# delay_line.net
KiCad netlist of a schematic drawn in EAGLE
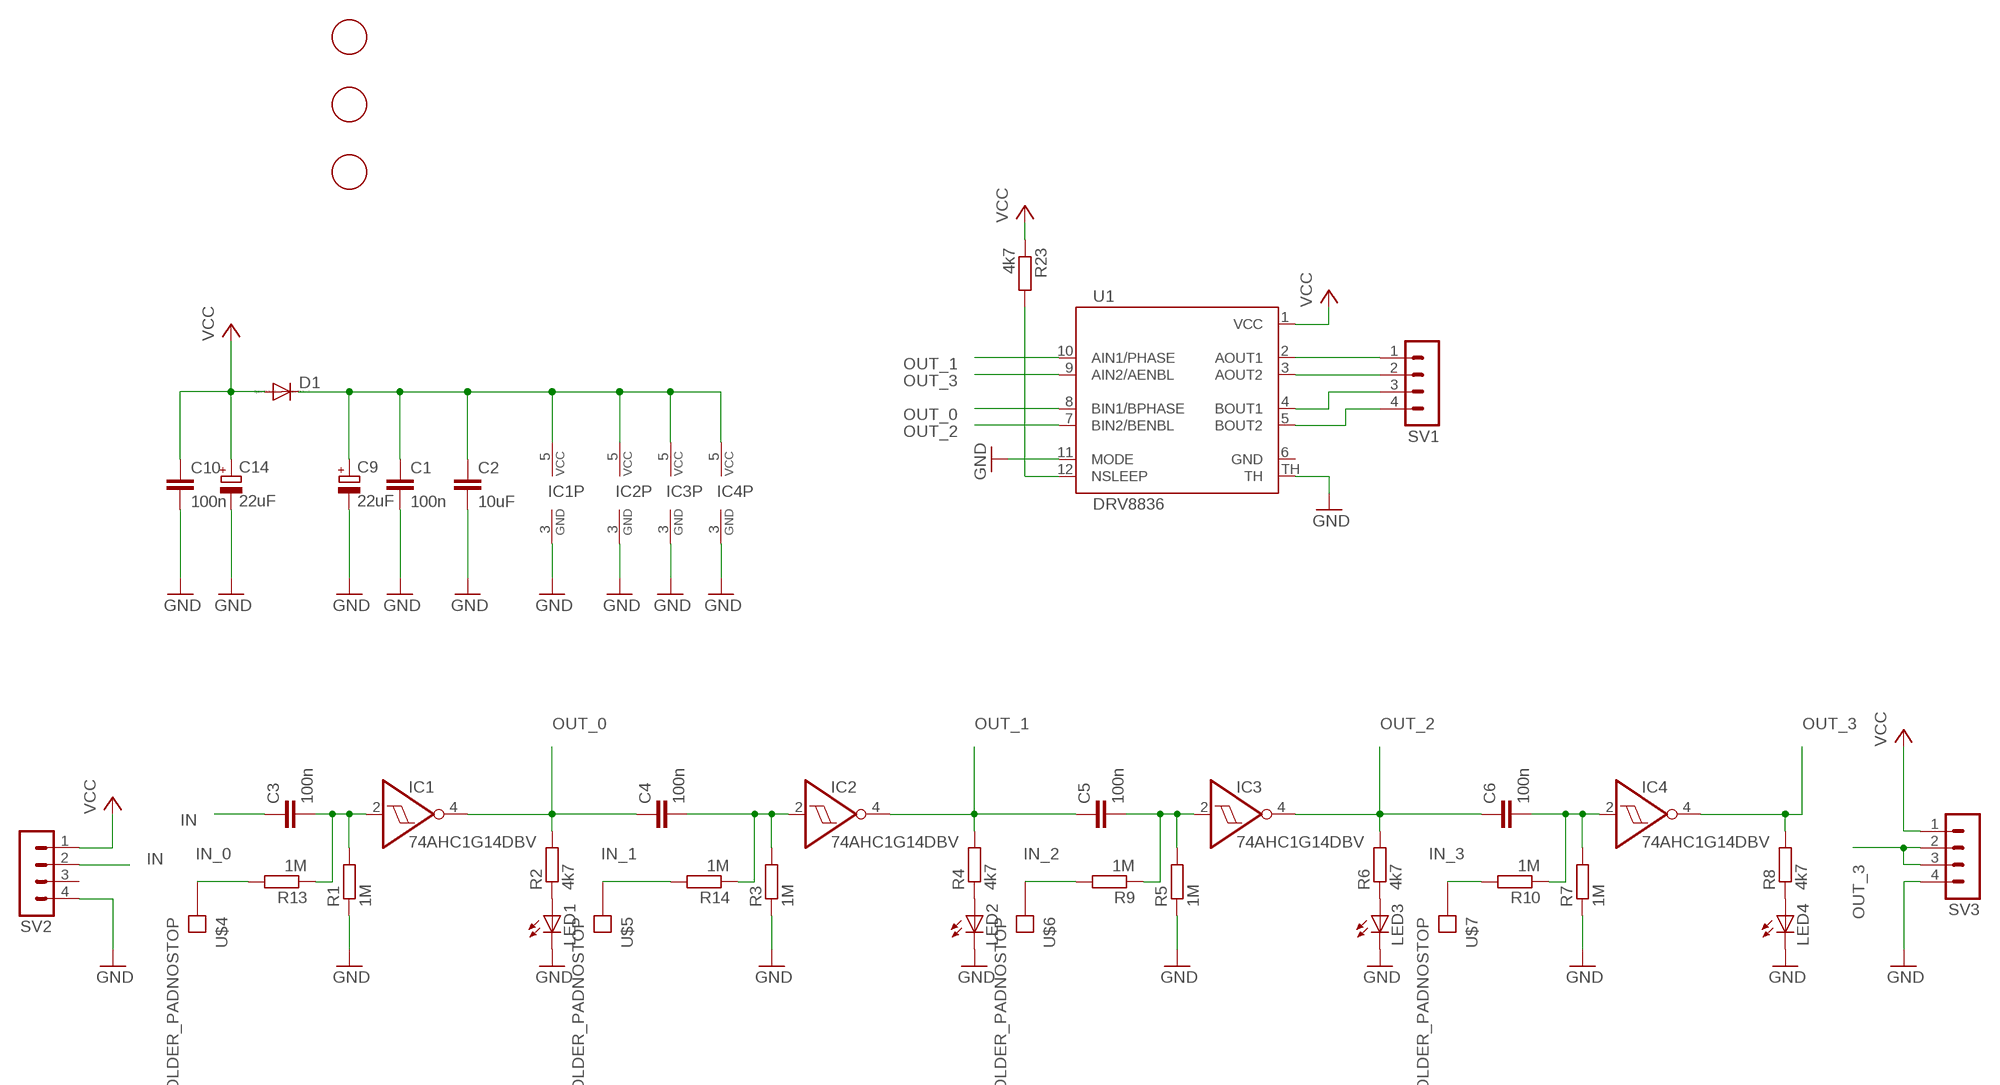
[diagram p0: schematic, sheet 1]

(export (version "E")
  (design (tool "Eeschema 10.0.6"))
  (components
    (comp (ref "C1")
      (value "100n")
      (footprint "eagle-import:C0805")
      (libsource (lib "eagle-import") (part "C-EUC0805"))
    )
    (comp (ref "C2")
      (value "10uF")
      (footprint "eagle-import:C0805")
      (libsource (lib "eagle-import") (part "C-EUC0805"))
    )
    (comp (ref "C3")
      (value "100n")
      (footprint "eagle-import:C0805")
      (libsource (lib "eagle-import") (part "C-EUC0805"))
    )
    (comp (ref "C4")
      (value "100n")
      (footprint "eagle-import:C0805")
      (libsource (lib "eagle-import") (part "C-EUC0805"))
    )
    (comp (ref "C5")
      (value "100n")
      (footprint "eagle-import:C0805")
      (libsource (lib "eagle-import") (part "C-EUC0805"))
    )
    (comp (ref "C6")
      (value "100n")
      (footprint "eagle-import:C0805")
      (libsource (lib "eagle-import") (part "C-EUC0805"))
    )
    (comp (ref "C9")
      (value "22uF")
      (footprint "eagle-import:153CLV-0605")
      (libsource (lib "eagle-import") (part "CPOL-EU153CLV-0605"))
    )
    (comp (ref "C10")
      (value "100n")
      (footprint "eagle-import:C0805")
      (libsource (lib "eagle-import") (part "C-EUC0805"))
    )
    (comp (ref "C14")
      (value "22uF")
      (footprint "eagle-import:153CLV-0605")
      (libsource (lib "eagle-import") (part "CPOL-EU153CLV-0605"))
    )
    (comp (ref "D1")
      (value "DIODE-DO214AA")
      (footprint "eagle-import:DO214AA")
      (libsource (lib "eagle-import") (part "DIODE-DO214AA"))
    )
    (comp (ref "IC1")
      (value "74AHC1G14DBV")
      (footprint "eagle-import:SOT23-5")
      (libsource (lib "eagle-import") (part "741G14DBVAHC"))
    )
    (comp (ref "IC2")
      (value "74AHC1G14DBV")
      (footprint "eagle-import:SOT23-5")
      (libsource (lib "eagle-import") (part "741G14DBVAHC"))
    )
    (comp (ref "IC3")
      (value "74AHC1G14DBV")
      (footprint "eagle-import:SOT23-5")
      (libsource (lib "eagle-import") (part "741G14DBVAHC"))
    )
    (comp (ref "IC4")
      (value "74AHC1G14DBV")
      (footprint "eagle-import:SOT23-5")
      (libsource (lib "eagle-import") (part "741G14DBVAHC"))
    )
    (comp (ref "LED1")
      (value "LEDSML1206")
      (footprint "eagle-import:SML1206")
      (libsource (lib "eagle-import") (part "LEDSML1206"))
    )
    (comp (ref "LED2")
      (value "LEDSML1206")
      (footprint "eagle-import:SML1206")
      (libsource (lib "eagle-import") (part "LEDSML1206"))
    )
    (comp (ref "LED3")
      (value "LEDSML1206")
      (footprint "eagle-import:SML1206")
      (libsource (lib "eagle-import") (part "LEDSML1206"))
    )
    (comp (ref "LED4")
      (value "LEDSML1206")
      (footprint "eagle-import:SML1206")
      (libsource (lib "eagle-import") (part "LEDSML1206"))
    )
    (comp (ref "R1")
      (value "1M")
      (footprint "eagle-import:M0805")
      (libsource (lib "eagle-import") (part "R-EU_M0805"))
    )
    (comp (ref "R2")
      (value "4k7")
      (footprint "eagle-import:M0805")
      (libsource (lib "eagle-import") (part "R-EU_M0805"))
    )
    (comp (ref "R3")
      (value "1M")
      (footprint "eagle-import:M0805")
      (libsource (lib "eagle-import") (part "R-EU_M0805"))
    )
    (comp (ref "R4")
      (value "4k7")
      (footprint "eagle-import:M0805")
      (libsource (lib "eagle-import") (part "R-EU_M0805"))
    )
    (comp (ref "R5")
      (value "1M")
      (footprint "eagle-import:M0805")
      (libsource (lib "eagle-import") (part "R-EU_M0805"))
    )
    (comp (ref "R6")
      (value "4k7")
      (footprint "eagle-import:M0805")
      (libsource (lib "eagle-import") (part "R-EU_M0805"))
    )
    (comp (ref "R7")
      (value "1M")
      (footprint "eagle-import:M0805")
      (libsource (lib "eagle-import") (part "R-EU_M0805"))
    )
    (comp (ref "R8")
      (value "4k7")
      (footprint "eagle-import:M0805")
      (libsource (lib "eagle-import") (part "R-EU_M0805"))
    )
    (comp (ref "R9")
      (value "1M")
      (footprint "eagle-import:M0805")
      (libsource (lib "eagle-import") (part "R-EU_M0805"))
    )
    (comp (ref "R10")
      (value "1M")
      (footprint "eagle-import:M0805")
      (libsource (lib "eagle-import") (part "R-EU_M0805"))
    )
    (comp (ref "R13")
      (value "1M")
      (footprint "eagle-import:M0805")
      (libsource (lib "eagle-import") (part "R-EU_M0805"))
    )
    (comp (ref "R14")
      (value "1M")
      (footprint "eagle-import:M0805")
      (libsource (lib "eagle-import") (part "R-EU_M0805"))
    )
    (comp (ref "R23")
      (value "4k7")
      (footprint "eagle-import:M0805")
      (libsource (lib "eagle-import") (part "R-EU_M0805"))
    )
    (comp (ref "SV1")
      (value "MA04-1")
      (footprint "eagle-import:MA04-1")
      (libsource (lib "eagle-import") (part "MA04-1"))
    )
    (comp (ref "SV2")
      (value "MA04-1")
      (footprint "eagle-import:MA04-1")
      (libsource (lib "eagle-import") (part "MA04-1"))
    )
    (comp (ref "SV3")
      (value "MA04-1")
      (footprint "eagle-import:MA04-1")
      (libsource (lib "eagle-import") (part "MA04-1"))
    )
    (comp (ref "U$1")
      (value "ADAFRUIT_FIDUCIAL")
      (footprint "eagle-import:ADAFRUIT_FIDUCIAL_1MM")
      (libsource (lib "eagle-import") (part "ADAFRUIT_FIDUCIAL"))
    )
    (comp (ref "U$2")
      (value "ADAFRUIT_FIDUCIAL")
      (footprint "eagle-import:ADAFRUIT_FIDUCIAL_1MM")
      (libsource (lib "eagle-import") (part "ADAFRUIT_FIDUCIAL"))
    )
    (comp (ref "U$3")
      (value "ADAFRUIT_FIDUCIAL")
      (footprint "eagle-import:ADAFRUIT_FIDUCIAL_1MM")
      (libsource (lib "eagle-import") (part "ADAFRUIT_FIDUCIAL"))
    )
    (comp (ref "U$4")
      (value "SOLDER_PADNOSTOP")
      (footprint "eagle-import:SOLDER_PAD_NOSTOP")
      (libsource (lib "eagle-import") (part "SOLDER_PADNOSTOP"))
    )
    (comp (ref "U$5")
      (value "SOLDER_PADNOSTOP")
      (footprint "eagle-import:SOLDER_PAD_NOSTOP")
      (libsource (lib "eagle-import") (part "SOLDER_PADNOSTOP"))
    )
    (comp (ref "U$6")
      (value "SOLDER_PADNOSTOP")
      (footprint "eagle-import:SOLDER_PAD_NOSTOP")
      (libsource (lib "eagle-import") (part "SOLDER_PADNOSTOP"))
    )
    (comp (ref "U$7")
      (value "SOLDER_PADNOSTOP")
      (footprint "eagle-import:SOLDER_PAD_NOSTOP")
      (libsource (lib "eagle-import") (part "SOLDER_PADNOSTOP"))
    )
    (comp (ref "U1")
      (value "DRV8836")
      (footprint "eagle-import:12WSON")
      (libsource (lib "eagle-import") (part "DRV8836"))
    )
  )
  (nets
    (net (code "1") (name "/IN") (class "Default")
      (node (ref "C3") (pin "1") (pinfunction "1_1") (pintype "passive"))
      (node (ref "SV2") (pin "2") (pinfunction "2_2") (pintype "passive"))
    )
    (net (code "2") (name "/IN_0") (class "Default")
      (node (ref "R13") (pin "2") (pinfunction "2_2") (pintype "passive"))
      (node (ref "U$4") (pin "SPAD") (pinfunction "NET_SPAD") (pintype "bidirectional"))
    )
    (net (code "3") (name "/IN_1") (class "Default")
      (node (ref "R14") (pin "2") (pinfunction "2_2") (pintype "passive"))
      (node (ref "U$5") (pin "SPAD") (pinfunction "NET_SPAD") (pintype "bidirectional"))
    )
    (net (code "4") (name "/IN_2") (class "Default")
      (node (ref "R9") (pin "2") (pinfunction "2_2") (pintype "passive"))
      (node (ref "U$6") (pin "SPAD") (pinfunction "NET_SPAD") (pintype "bidirectional"))
    )
    (net (code "5") (name "/IN_3") (class "Default")
      (node (ref "R10") (pin "2") (pinfunction "2_2") (pintype "passive"))
      (node (ref "U$7") (pin "SPAD") (pinfunction "NET_SPAD") (pintype "bidirectional"))
    )
    (net (code "6") (name "/OUT_0") (class "Default")
      (node (ref "C4") (pin "1") (pinfunction "1_1") (pintype "passive"))
      (node (ref "IC1") (pin "4") (pinfunction "O_4") (pintype "output"))
      (node (ref "R2") (pin "2") (pinfunction "2_2") (pintype "passive"))
      (node (ref "U1") (pin "8") (pinfunction "BIN1/BPHASE_8") (pintype "bidirectional"))
    )
    (net (code "7") (name "/OUT_1") (class "Default")
      (node (ref "C5") (pin "1") (pinfunction "1_1") (pintype "passive"))
      (node (ref "IC2") (pin "4") (pinfunction "O_4") (pintype "output"))
      (node (ref "R4") (pin "2") (pinfunction "2_2") (pintype "passive"))
      (node (ref "U1") (pin "10") (pinfunction "AIN1/PHASE_10") (pintype "bidirectional"))
    )
    (net (code "8") (name "/OUT_2") (class "Default")
      (node (ref "C6") (pin "1") (pinfunction "1_1") (pintype "passive"))
      (node (ref "IC3") (pin "4") (pinfunction "O_4") (pintype "output"))
      (node (ref "R6") (pin "2") (pinfunction "2_2") (pintype "passive"))
      (node (ref "U1") (pin "7") (pinfunction "BIN2/BENBL_7") (pintype "bidirectional"))
    )
    (net (code "9") (name "/OUT_3") (class "Default")
      (node (ref "IC4") (pin "4") (pinfunction "O_4") (pintype "output"))
      (node (ref "R8") (pin "2") (pinfunction "2_2") (pintype "passive"))
      (node (ref "SV3") (pin "2") (pinfunction "2_2") (pintype "passive"))
      (node (ref "SV3") (pin "3") (pinfunction "3_3") (pintype "passive"))
      (node (ref "U1") (pin "9") (pinfunction "AIN2/AENBL_9") (pintype "bidirectional"))
    )
    (net (code "10") (name "GND") (class "Default")
      (node (ref "C1") (pin "2") (pinfunction "2_2") (pintype "passive"))
      (node (ref "C10") (pin "2") (pinfunction "2_2") (pintype "passive"))
      (node (ref "C14") (pin "-") (pinfunction "-_-") (pintype "passive"))
      (node (ref "C2") (pin "2") (pinfunction "2_2") (pintype "passive"))
      (node (ref "C9") (pin "-") (pinfunction "-_-") (pintype "passive"))
      (node (ref "IC1") (pin "3") (pinfunction "GND_3") (pintype "power_in"))
      (node (ref "IC2") (pin "3") (pinfunction "GND_3") (pintype "power_in"))
      (node (ref "IC3") (pin "3") (pinfunction "GND_3") (pintype "power_in"))
      (node (ref "IC4") (pin "3") (pinfunction "GND_3") (pintype "power_in"))
      (node (ref "LED1") (pin "C") (pinfunction "C_C") (pintype "passive"))
      (node (ref "LED2") (pin "C") (pinfunction "C_C") (pintype "passive"))
      (node (ref "LED3") (pin "C") (pinfunction "C_C") (pintype "passive"))
      (node (ref "LED4") (pin "C") (pinfunction "C_C") (pintype "passive"))
      (node (ref "R1") (pin "1") (pinfunction "1_1") (pintype "passive"))
      (node (ref "R3") (pin "1") (pinfunction "1_1") (pintype "passive"))
      (node (ref "R5") (pin "1") (pinfunction "1_1") (pintype "passive"))
      (node (ref "R7") (pin "1") (pinfunction "1_1") (pintype "passive"))
      (node (ref "SV2") (pin "4") (pinfunction "4_4") (pintype "passive"))
      (node (ref "SV3") (pin "4") (pinfunction "4_4") (pintype "passive"))
      (node (ref "U1") (pin "11") (pinfunction "MODE_11") (pintype "bidirectional"))
      (node (ref "U1") (pin "TH") (pinfunction "TH_TH") (pintype "bidirectional"))
    )
    (net (code "11") (name "Net-(IC1A-I)") (class "Default")
      (node (ref "C3") (pin "2") (pinfunction "2_2") (pintype "passive"))
      (node (ref "IC1") (pin "2") (pinfunction "I_2") (pintype "input"))
      (node (ref "R1") (pin "2") (pinfunction "2_2") (pintype "passive"))
      (node (ref "R13") (pin "1") (pinfunction "1_1") (pintype "passive"))
    )
    (net (code "12") (name "Net-(IC1B-VCC)") (class "Default")
      (node (ref "C1") (pin "1") (pinfunction "1_1") (pintype "passive"))
      (node (ref "C2") (pin "1") (pinfunction "1_1") (pintype "passive"))
      (node (ref "C9") (pin "+") (pinfunction "+_+") (pintype "passive"))
      (node (ref "D1") (pin "C") (pinfunction "C_C") (pintype "passive"))
      (node (ref "IC1") (pin "5") (pinfunction "VCC_5") (pintype "power_in"))
      (node (ref "IC2") (pin "5") (pinfunction "VCC_5") (pintype "power_in"))
      (node (ref "IC3") (pin "5") (pinfunction "VCC_5") (pintype "power_in"))
      (node (ref "IC4") (pin "5") (pinfunction "VCC_5") (pintype "power_in"))
    )
    (net (code "13") (name "Net-(IC2A-I)") (class "Default")
      (node (ref "C4") (pin "2") (pinfunction "2_2") (pintype "passive"))
      (node (ref "IC2") (pin "2") (pinfunction "I_2") (pintype "input"))
      (node (ref "R14") (pin "1") (pinfunction "1_1") (pintype "passive"))
      (node (ref "R3") (pin "2") (pinfunction "2_2") (pintype "passive"))
    )
    (net (code "14") (name "Net-(IC3A-I)") (class "Default")
      (node (ref "C5") (pin "2") (pinfunction "2_2") (pintype "passive"))
      (node (ref "IC3") (pin "2") (pinfunction "I_2") (pintype "input"))
      (node (ref "R5") (pin "2") (pinfunction "2_2") (pintype "passive"))
      (node (ref "R9") (pin "1") (pinfunction "1_1") (pintype "passive"))
    )
    (net (code "15") (name "Net-(IC4A-I)") (class "Default")
      (node (ref "C6") (pin "2") (pinfunction "2_2") (pintype "passive"))
      (node (ref "IC4") (pin "2") (pinfunction "I_2") (pintype "input"))
      (node (ref "R10") (pin "1") (pinfunction "1_1") (pintype "passive"))
      (node (ref "R7") (pin "2") (pinfunction "2_2") (pintype "passive"))
    )
    (net (code "16") (name "Net-(LED1-PadA)") (class "Default")
      (node (ref "LED1") (pin "A") (pinfunction "A_A") (pintype "passive"))
      (node (ref "R2") (pin "1") (pinfunction "1_1") (pintype "passive"))
    )
    (net (code "17") (name "Net-(LED2-PadA)") (class "Default")
      (node (ref "LED2") (pin "A") (pinfunction "A_A") (pintype "passive"))
      (node (ref "R4") (pin "1") (pinfunction "1_1") (pintype "passive"))
    )
    (net (code "18") (name "Net-(LED3-PadA)") (class "Default")
      (node (ref "LED3") (pin "A") (pinfunction "A_A") (pintype "passive"))
      (node (ref "R6") (pin "1") (pinfunction "1_1") (pintype "passive"))
    )
    (net (code "19") (name "Net-(LED4-PadA)") (class "Default")
      (node (ref "LED4") (pin "A") (pinfunction "A_A") (pintype "passive"))
      (node (ref "R8") (pin "1") (pinfunction "1_1") (pintype "passive"))
    )
    (net (code "20") (name "Net-(U1-AOUT1)") (class "Default")
      (node (ref "SV1") (pin "1") (pinfunction "1_1") (pintype "passive"))
      (node (ref "U1") (pin "2") (pinfunction "AOUT1_2") (pintype "bidirectional"))
    )
    (net (code "21") (name "Net-(U1-AOUT2)") (class "Default")
      (node (ref "SV1") (pin "2") (pinfunction "2_2") (pintype "passive"))
      (node (ref "U1") (pin "3") (pinfunction "AOUT2_3") (pintype "bidirectional"))
    )
    (net (code "22") (name "Net-(U1-BOUT1)") (class "Default")
      (node (ref "SV1") (pin "3") (pinfunction "3_3") (pintype "passive"))
      (node (ref "U1") (pin "4") (pinfunction "BOUT1_4") (pintype "bidirectional"))
    )
    (net (code "23") (name "Net-(U1-BOUT2)") (class "Default")
      (node (ref "SV1") (pin "4") (pinfunction "4_4") (pintype "passive"))
      (node (ref "U1") (pin "5") (pinfunction "BOUT2_5") (pintype "bidirectional"))
    )
    (net (code "24") (name "Net-(U1-NSLEEP)") (class "Default")
      (node (ref "R23") (pin "2") (pinfunction "2_2") (pintype "passive"))
      (node (ref "U1") (pin "12") (pinfunction "NSLEEP_12") (pintype "bidirectional"))
    )
    (net (code "25") (name "VCC") (class "Default")
      (node (ref "C10") (pin "1") (pinfunction "1_1") (pintype "passive"))
      (node (ref "C14") (pin "+") (pinfunction "+_+") (pintype "passive"))
      (node (ref "D1") (pin "A") (pinfunction "A_A") (pintype "passive"))
      (node (ref "R23") (pin "1") (pinfunction "1_1") (pintype "passive"))
      (node (ref "SV2") (pin "1") (pinfunction "1_1") (pintype "passive"))
      (node (ref "SV3") (pin "1") (pinfunction "1_1") (pintype "passive"))
      (node (ref "U1") (pin "1") (pinfunction "VCC_1") (pintype "bidirectional"))
    )
    (net (code "26") (name "unconnected-(SV2-Pad3)") (class "Default")
      (node (ref "SV2") (pin "3") (pinfunction "3_3") (pintype "passive"))
    )
    (net (code "27") (name "unconnected-(U1-GND-Pad6)") (class "Default")
      (node (ref "U1") (pin "6") (pinfunction "GND_6") (pintype "bidirectional"))
    )
  )
)
